# CANTerm.net
KiCad netlist of a schematic drawn in Altium Designer
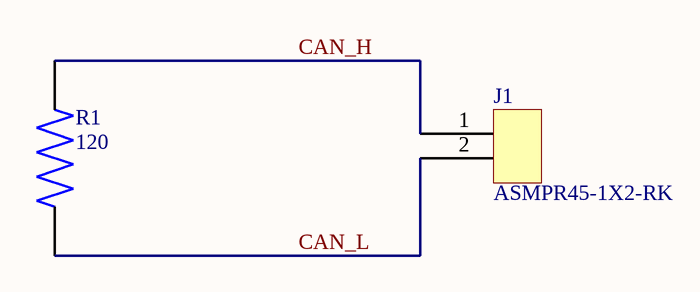
[diagram p0: CANTerm.SchDoc]

(export (version "E")
  (design (tool "Eeschema 10.0.6"))
  (components
    (comp (ref "J1")
      (value "ASMPR45-1X2-RK")
      (footprint "APP_ASMPR45-1X2-RK")
      (description "C-powerpoles 10 / 45, PP15/45 1X2 45 Amp Horizontal Pcb Assembly Red, Blk.")
      (fields (field (name "MANUFACTURER") "Anderson Power"))
      (libsource (lib "CANTerm") (part "ASMPR45-1X2-RK"))
    )
    (comp (ref "R1")
      (value "120")
      (footprint "R0805")
      (description "Fixed Resistor CRGCQ 0805 120R 1%")
      (fields (field (name "MP") "CRGCQ0805F120R") (field (name "MF") "TE Connectivity"))
      (libsource (lib "CANTerm") (part "CRGCQ0805F120R"))
    )
  )
  (nets
    (net (code "1") (name "/CAN_H") (class "Default")
      (node (ref "J1") (pin "1") (pinfunction "1_1") (pintype "passive"))
      (node (ref "R1") (pin "2") (pinfunction "2_2") (pintype "passive"))
    )
    (net (code "2") (name "/CAN_L") (class "Default")
      (node (ref "J1") (pin "2") (pinfunction "2_2") (pintype "passive"))
      (node (ref "R1") (pin "1") (pinfunction "1_1") (pintype "passive"))
    )
  )
)
